# ProDoc_24G_HOST_2026-09-22.net
KiCad netlist of a schematic drawn in EasyEDA Pro
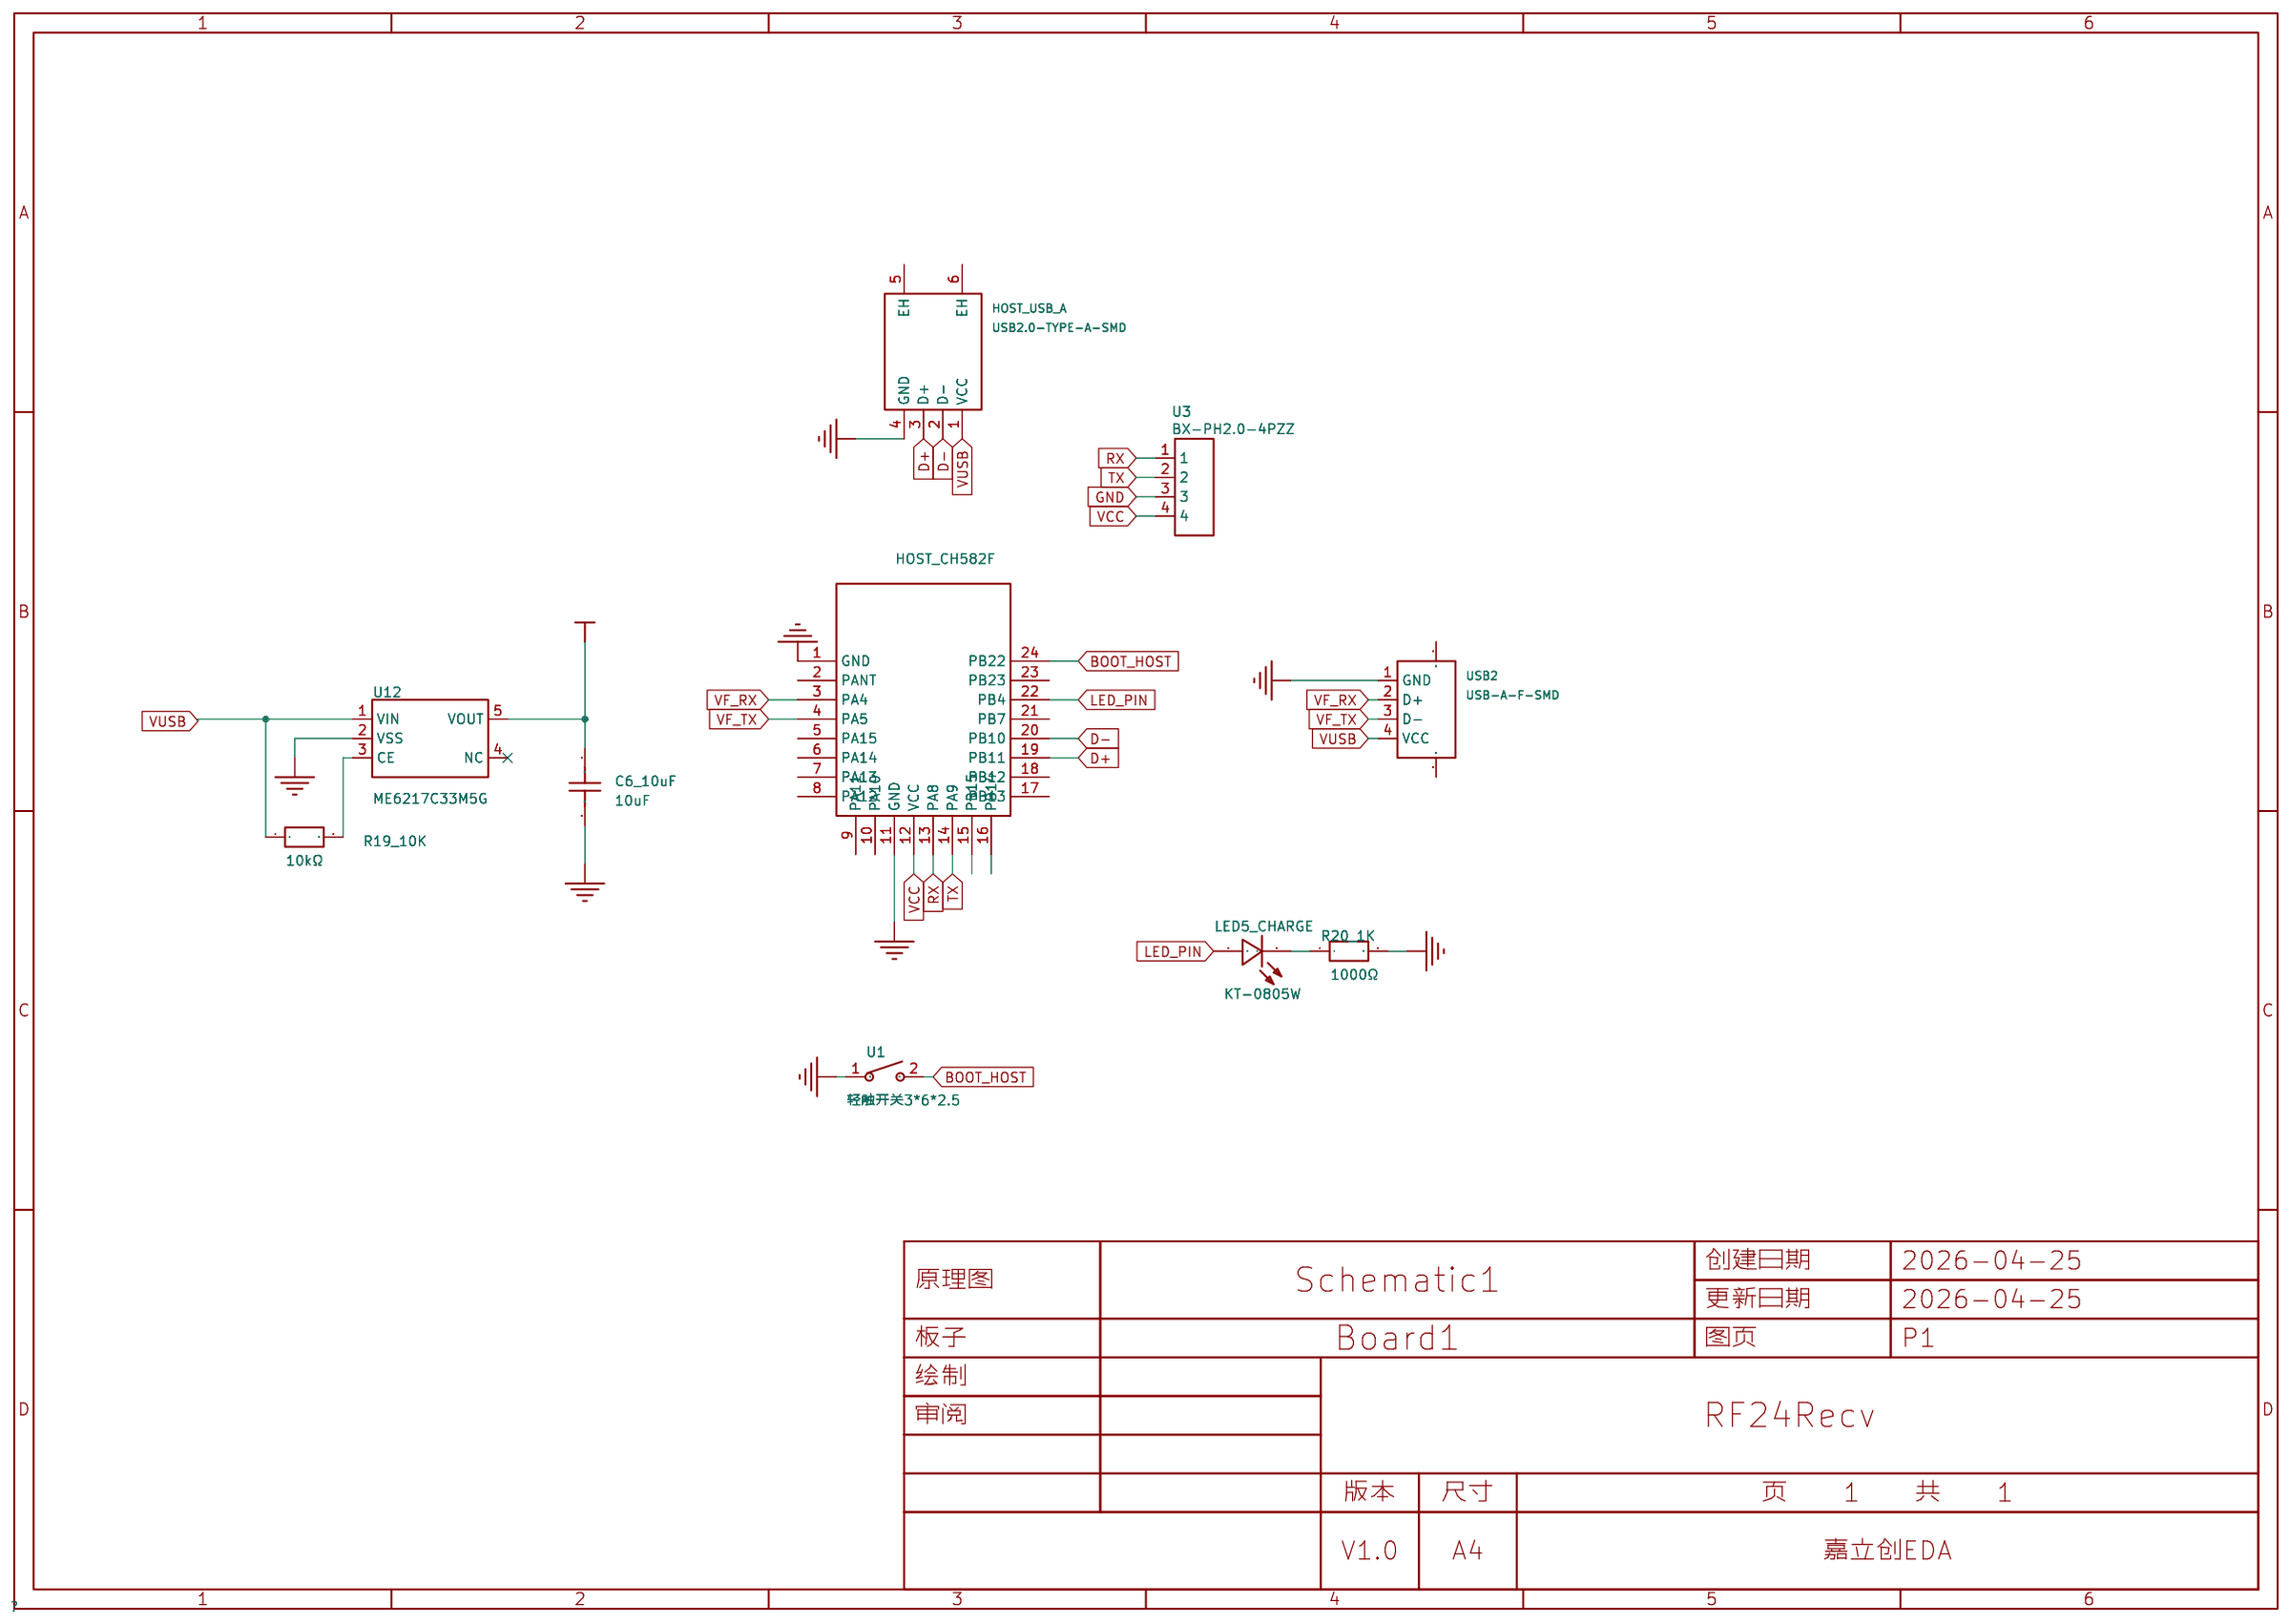
[diagram p0: schematic sheet]

(export (version "E")
  (design (tool "Eeschema 10.0.6"))
  (components
    (comp (ref "C6_10uF")
      (value "10uF")
      (footprint "easyedapro:C0805")
      (description "容值:10uF;精度:±10%;额定电压:25V;温度系数:X5R;")
      (fields
        (field (name "Manufacturer Part") "CL21A106KAYNNNE")
        (field (name "Manufacturer") "SAMSUNG(三星)")
      )
      (libsource (lib "easyedapro") (part "CL21A106KAYNNNE"))
    )
    (comp (ref "HOST_CH582F")
      (value "~")
      (footprint "easyedapro:ch582f")
      (libsource (lib "easyedapro") (part "ch582f"))
    )
    (comp (ref "HOST_USB_A")
      (value "USB2.0-TYPE-A-SMD")
      (footprint "easyedapro:USB2.0-TYPE-A-4P-SMD")
      (fields (field (name "Manufacturer Part") "USB-07") (field (name "Manufacturer") "SOFNG"))
      (libsource (lib "easyedapro") (part "USB2.0-TYPE-A-SMD"))
    )
    (comp (ref "LED5_CHARGE")
      (value "KT-0805W")
      (footprint "easyedapro:LED0805-R-RD")
      (description "色温6000K左右")
      (fields (field (name "Manufacturer") "KENTO"))
      (libsource (lib "easyedapro") (part "whiteLEDSMD"))
    )
    (comp (ref "R19_10K")
      (value "10kΩ")
      (footprint "easyedapro:R0805")
      (fields
        (field (name "Manufacturer Part") "SC0805J1002F4ANRH")
        (field (name "Manufacturer") "Sunway(信维通信)")
        (field (name "Contributor") "lcsc")
      )
      (libsource (lib "easyedapro") (part "10kΩ"))
    )
    (comp (ref "R20_1K")
      (value "1000Ω")
      (footprint "easyedapro:R0805")
      (description "电阻类型:薄膜电阻;阻值:100Ω;精度:±0.5%;功率:250mW;最大工作电压:150V;温度系数:±25ppm/℃;")
      (fields (field (name "Manufacturer Part") "TC0525D1000T5E") (field (name "Tolerance") "±0.5%"))
      (libsource (lib "easyedapro") (part "TC0525D1000T5E_C44786"))
    )
    (comp (ref "U1")
      (value "轻触开关3*6*2.5")
      (footprint "easyedapro:SW-SMD_L6.1-W3.6-LS7.9")
      (libsource (lib "easyedapro") (part "轻触开关3*6*2.5"))
    )
    (comp (ref "U3")
      (value "BX-PH2.0-4PZZ")
      (footprint "easyedapro:CONN-TH_4P-P2.00_BX-PH2.0-4PZZ")
      (fields (field (name "Manufacturer") "Bossie(博锡)") (field (name "Contributor") "lcsc"))
      (libsource (lib "easyedapro") (part "BX-PH2.0-4PZZ"))
    )
    (comp (ref "U12")
      (value "ME6217C33M5G")
      (footprint "easyedapro:SOT-23-5_L3.0-W1.7-P0.95-LS2.8-BR")
      (description "输出类型:固定;工作电压:6.5V;输出电压:3.3V;输出电流:800mA;电源纹波抑制比(PSRR):65dB@(1kHz);输出极性:正极;")
      (fields (field (name "Manufacturer") "MICRONE(南京微盟)"))
      (libsource (lib "easyedapro") (part "ME6217C33M5G"))
    )
    (comp (ref "USB2")
      (value "USB-A-F-SMD")
      (footprint "easyedapro:USB-TYPEA_F_SMD")
      (libsource (lib "easyedapro") (part "USB-A-F-SMD"))
    )
  )
  (nets
    (net (code "1") (name "BOOT_HOST") (class "Default")
      (node (ref "HOST_CH582F") (pin "24") (pinfunction "PB22_24") (pintype "unspecified"))
      (node (ref "U1") (pin "2") (pinfunction "2_2") (pintype "unspecified"))
    )
    (net (code "2") (name "D+") (class "Default")
      (node (ref "HOST_CH582F") (pin "19") (pinfunction "PB11_19") (pintype "unspecified"))
      (node (ref "HOST_USB_A") (pin "3") (pinfunction "D+_3") (pintype "input"))
    )
    (net (code "3") (name "D-") (class "Default")
      (node (ref "HOST_CH582F") (pin "20") (pinfunction "PB10_20") (pintype "unspecified"))
      (node (ref "HOST_USB_A") (pin "2") (pinfunction "D-_2") (pintype "input"))
    )
    (net (code "4") (name "GND") (class "Default")
      (node (ref "C6_10uF") (pin "2") (pinfunction "2_2") (pintype "unspecified"))
      (node (ref "HOST_CH582F") (pin "1") (pinfunction "GND_1") (pintype "unspecified"))
      (node (ref "HOST_CH582F") (pin "11") (pinfunction "GND_11") (pintype "unspecified"))
      (node (ref "HOST_USB_A") (pin "4") (pinfunction "GND_4") (pintype "input"))
      (node (ref "R20_1K") (pin "2") (pinfunction "2_2") (pintype "unspecified"))
      (node (ref "U1") (pin "1") (pinfunction "1_1") (pintype "unspecified"))
      (node (ref "U12") (pin "2") (pinfunction "VSS_2") (pintype "unspecified"))
      (node (ref "U3") (pin "3") (pinfunction "3_3") (pintype "unspecified"))
      (node (ref "USB2") (pin "1") (pinfunction "GND_1") (pintype "unspecified"))
    )
    (net (code "5") (name "LED_PIN") (class "Default")
      (node (ref "HOST_CH582F") (pin "22") (pinfunction "PB4_22") (pintype "unspecified"))
      (node (ref "LED5_CHARGE") (pin "1") (pinfunction "A_1") (pintype "unspecified"))
    )
    (net (code "6") (name "Net-(LED5_CHARGE-K)") (class "Default")
      (node (ref "LED5_CHARGE") (pin "2") (pinfunction "K_2") (pintype "unspecified"))
      (node (ref "R20_1K") (pin "1") (pinfunction "1_1") (pintype "unspecified"))
    )
    (net (code "7") (name "Net-(U12-CE)") (class "Default")
      (node (ref "R19_10K") (pin "2") (pinfunction "2_2") (pintype "unspecified"))
      (node (ref "U12") (pin "3") (pinfunction "CE_3") (pintype "unspecified"))
    )
    (net (code "8") (name "RX") (class "Default")
      (node (ref "HOST_CH582F") (pin "13") (pinfunction "PA8_13") (pintype "unspecified"))
      (node (ref "U3") (pin "1") (pinfunction "1_1") (pintype "unspecified"))
    )
    (net (code "9") (name "TX") (class "Default")
      (node (ref "HOST_CH582F") (pin "14") (pinfunction "PA9_14") (pintype "unspecified"))
      (node (ref "U3") (pin "2") (pinfunction "2_2") (pintype "unspecified"))
    )
    (net (code "10") (name "VCC") (class "Default")
      (node (ref "C6_10uF") (pin "1") (pinfunction "1_1") (pintype "unspecified"))
      (node (ref "HOST_CH582F") (pin "12") (pinfunction "VCC_12") (pintype "unspecified"))
      (node (ref "U12") (pin "5") (pinfunction "VOUT_5") (pintype "unspecified"))
      (node (ref "U3") (pin "4") (pinfunction "4_4") (pintype "unspecified"))
    )
    (net (code "11") (name "VF_RX") (class "Default")
      (node (ref "HOST_CH582F") (pin "3") (pinfunction "PA4_3") (pintype "unspecified"))
      (node (ref "USB2") (pin "2") (pinfunction "D+_2") (pintype "unspecified"))
    )
    (net (code "12") (name "VF_TX") (class "Default")
      (node (ref "HOST_CH582F") (pin "4") (pinfunction "PA5_4") (pintype "unspecified"))
      (node (ref "USB2") (pin "3") (pinfunction "D-_3") (pintype "unspecified"))
    )
    (net (code "13") (name "VUSB") (class "Default")
      (node (ref "HOST_USB_A") (pin "1") (pinfunction "VCC_1") (pintype "input"))
      (node (ref "R19_10K") (pin "1") (pinfunction "1_1") (pintype "unspecified"))
      (node (ref "U12") (pin "1") (pinfunction "VIN_1") (pintype "unspecified"))
      (node (ref "USB2") (pin "4") (pinfunction "VCC_4") (pintype "unspecified"))
    )
    (net (code "14") (name "unconnected-(HOST_CH582F-PA10-Pad10)") (class "Default")
      (node (ref "HOST_CH582F") (pin "10") (pinfunction "PA10_10") (pintype "unspecified"))
    )
    (net (code "15") (name "unconnected-(HOST_CH582F-PA11-Pad9)") (class "Default")
      (node (ref "HOST_CH582F") (pin "9") (pinfunction "PA11_9") (pintype "unspecified"))
    )
    (net (code "16") (name "unconnected-(HOST_CH582F-PA12-Pad8)") (class "Default")
      (node (ref "HOST_CH582F") (pin "8") (pinfunction "PA12_8") (pintype "unspecified"))
    )
    (net (code "17") (name "unconnected-(HOST_CH582F-PA13-Pad7)") (class "Default")
      (node (ref "HOST_CH582F") (pin "7") (pinfunction "PA13_7") (pintype "unspecified"))
    )
    (net (code "18") (name "unconnected-(HOST_CH582F-PA14-Pad6)") (class "Default")
      (node (ref "HOST_CH582F") (pin "6") (pinfunction "PA14_6") (pintype "unspecified"))
    )
    (net (code "19") (name "unconnected-(HOST_CH582F-PA15-Pad5)") (class "Default")
      (node (ref "HOST_CH582F") (pin "5") (pinfunction "PA15_5") (pintype "unspecified"))
    )
    (net (code "20") (name "unconnected-(HOST_CH582F-PANT-Pad2)") (class "Default")
      (node (ref "HOST_CH582F") (pin "2") (pinfunction "PANT_2") (pintype "unspecified"))
    )
    (net (code "21") (name "unconnected-(HOST_CH582F-PB7-Pad21)") (class "Default")
      (node (ref "HOST_CH582F") (pin "21") (pinfunction "PB7_21") (pintype "unspecified"))
    )
    (net (code "22") (name "unconnected-(HOST_CH582F-PB12-Pad18)") (class "Default")
      (node (ref "HOST_CH582F") (pin "18") (pinfunction "PB12_18") (pintype "unspecified"))
    )
    (net (code "23") (name "unconnected-(HOST_CH582F-PB13-Pad17)") (class "Default")
      (node (ref "HOST_CH582F") (pin "17") (pinfunction "PB13_17") (pintype "unspecified"))
    )
    (net (code "24") (name "unconnected-(HOST_CH582F-PB14-Pad16)") (class "Default")
      (node (ref "HOST_CH582F") (pin "16") (pinfunction "PB14_16") (pintype "unspecified"))
    )
    (net (code "25") (name "unconnected-(HOST_CH582F-PB15-Pad15)") (class "Default")
      (node (ref "HOST_CH582F") (pin "15") (pinfunction "PB15_15") (pintype "unspecified"))
    )
    (net (code "26") (name "unconnected-(HOST_CH582F-PB23-Pad23)") (class "Default")
      (node (ref "HOST_CH582F") (pin "23") (pinfunction "PB23_23") (pintype "unspecified"))
    )
    (net (code "27") (name "unconnected-(HOST_USB_A-EH-Pad5)") (class "Default")
      (node (ref "HOST_USB_A") (pin "5") (pinfunction "EH_5") (pintype "unspecified"))
    )
    (net (code "28") (name "unconnected-(HOST_USB_A-EH-Pad6)") (class "Default")
      (node (ref "HOST_USB_A") (pin "6") (pinfunction "EH_6") (pintype "unspecified"))
    )
    (net (code "29") (name "unconnected-(U12-NC-Pad4)") (class "Default")
      (node (ref "U12") (pin "4") (pinfunction "NC_4") (pintype "unspecified+no_connect"))
    )
    (net (code "30") (name "unconnected-(USB2-GND-Pad5)") (class "Default")
      (node (ref "USB2") (pin "5") (pinfunction "GND_5") (pintype "unspecified"))
    )
    (net (code "31") (name "unconnected-(USB2-GND-Pad6)") (class "Default")
      (node (ref "USB2") (pin "6") (pinfunction "GND_6") (pintype "unspecified"))
    )
  )
)
